# pwm.net
KiCad netlist of a schematic drawn in EAGLE
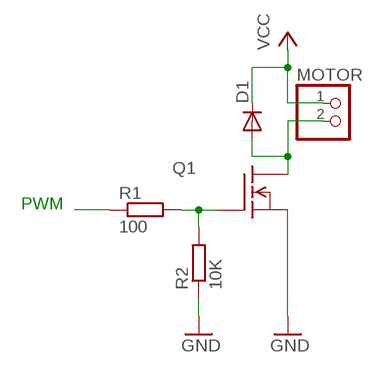
[diagram p0: schematic, sheet 1]

(export (version "E")
  (design (tool "Eeschema 10.0.6"))
  (components
    (comp (ref "D1")
      (value "1N4933")
      (footprint "eagle-import:DO41-10")
      (libsource (lib "eagle-import") (part "1N4933"))
    )
    (comp (ref "MOTOR")
      (value "PINHD-1X2")
      (footprint "eagle-import:1X02")
      (libsource (lib "eagle-import") (part "PINHD-1X2"))
    )
    (comp (ref "Q1")
      (value "BUZ60")
      (footprint "eagle-import:TO220")
      (libsource (lib "eagle-import") (part "BUZ60"))
    )
    (comp (ref "R1")
      (value "100")
      (footprint "eagle-import:0207_10")
      (libsource (lib "eagle-import") (part "R-EU_0207/10"))
    )
    (comp (ref "R2")
      (value "10K")
      (footprint "eagle-import:0207_10")
      (libsource (lib "eagle-import") (part "R-EU_0207/10"))
    )
  )
  (nets
    (net (code "1") (name "GND") (class "Default")
      (node (ref "Q1") (pin "3") (pinfunction "S_3") (pintype "passive"))
      (node (ref "R2") (pin "1") (pinfunction "1_1") (pintype "passive"))
    )
    (net (code "2") (name "Net-(Q1-D)") (class "Default")
      (node (ref "D1") (pin "A") (pinfunction "A_A") (pintype "passive"))
      (node (ref "MOTOR") (pin "2") (pinfunction "2_2") (pintype "passive"))
      (node (ref "Q1") (pin "2") (pinfunction "D_2") (pintype "passive"))
    )
    (net (code "3") (name "Net-(Q1-G)") (class "Default")
      (node (ref "Q1") (pin "1") (pinfunction "G_1") (pintype "passive"))
      (node (ref "R1") (pin "2") (pinfunction "2_2") (pintype "passive"))
      (node (ref "R2") (pin "2") (pinfunction "2_2") (pintype "passive"))
    )
    (net (code "4") (name "VCC") (class "Default")
      (node (ref "D1") (pin "C") (pinfunction "C_C") (pintype "passive"))
      (node (ref "MOTOR") (pin "1") (pinfunction "1_1") (pintype "passive"))
    )
    (net (code "5") (name "unconnected-(R1-Pad1)") (class "Default")
      (node (ref "R1") (pin "1") (pinfunction "1_1") (pintype "passive"))
    )
  )
)
